# JETSON_PWR_MUX.net
KiCad netlist of a schematic drawn in Altium Designer
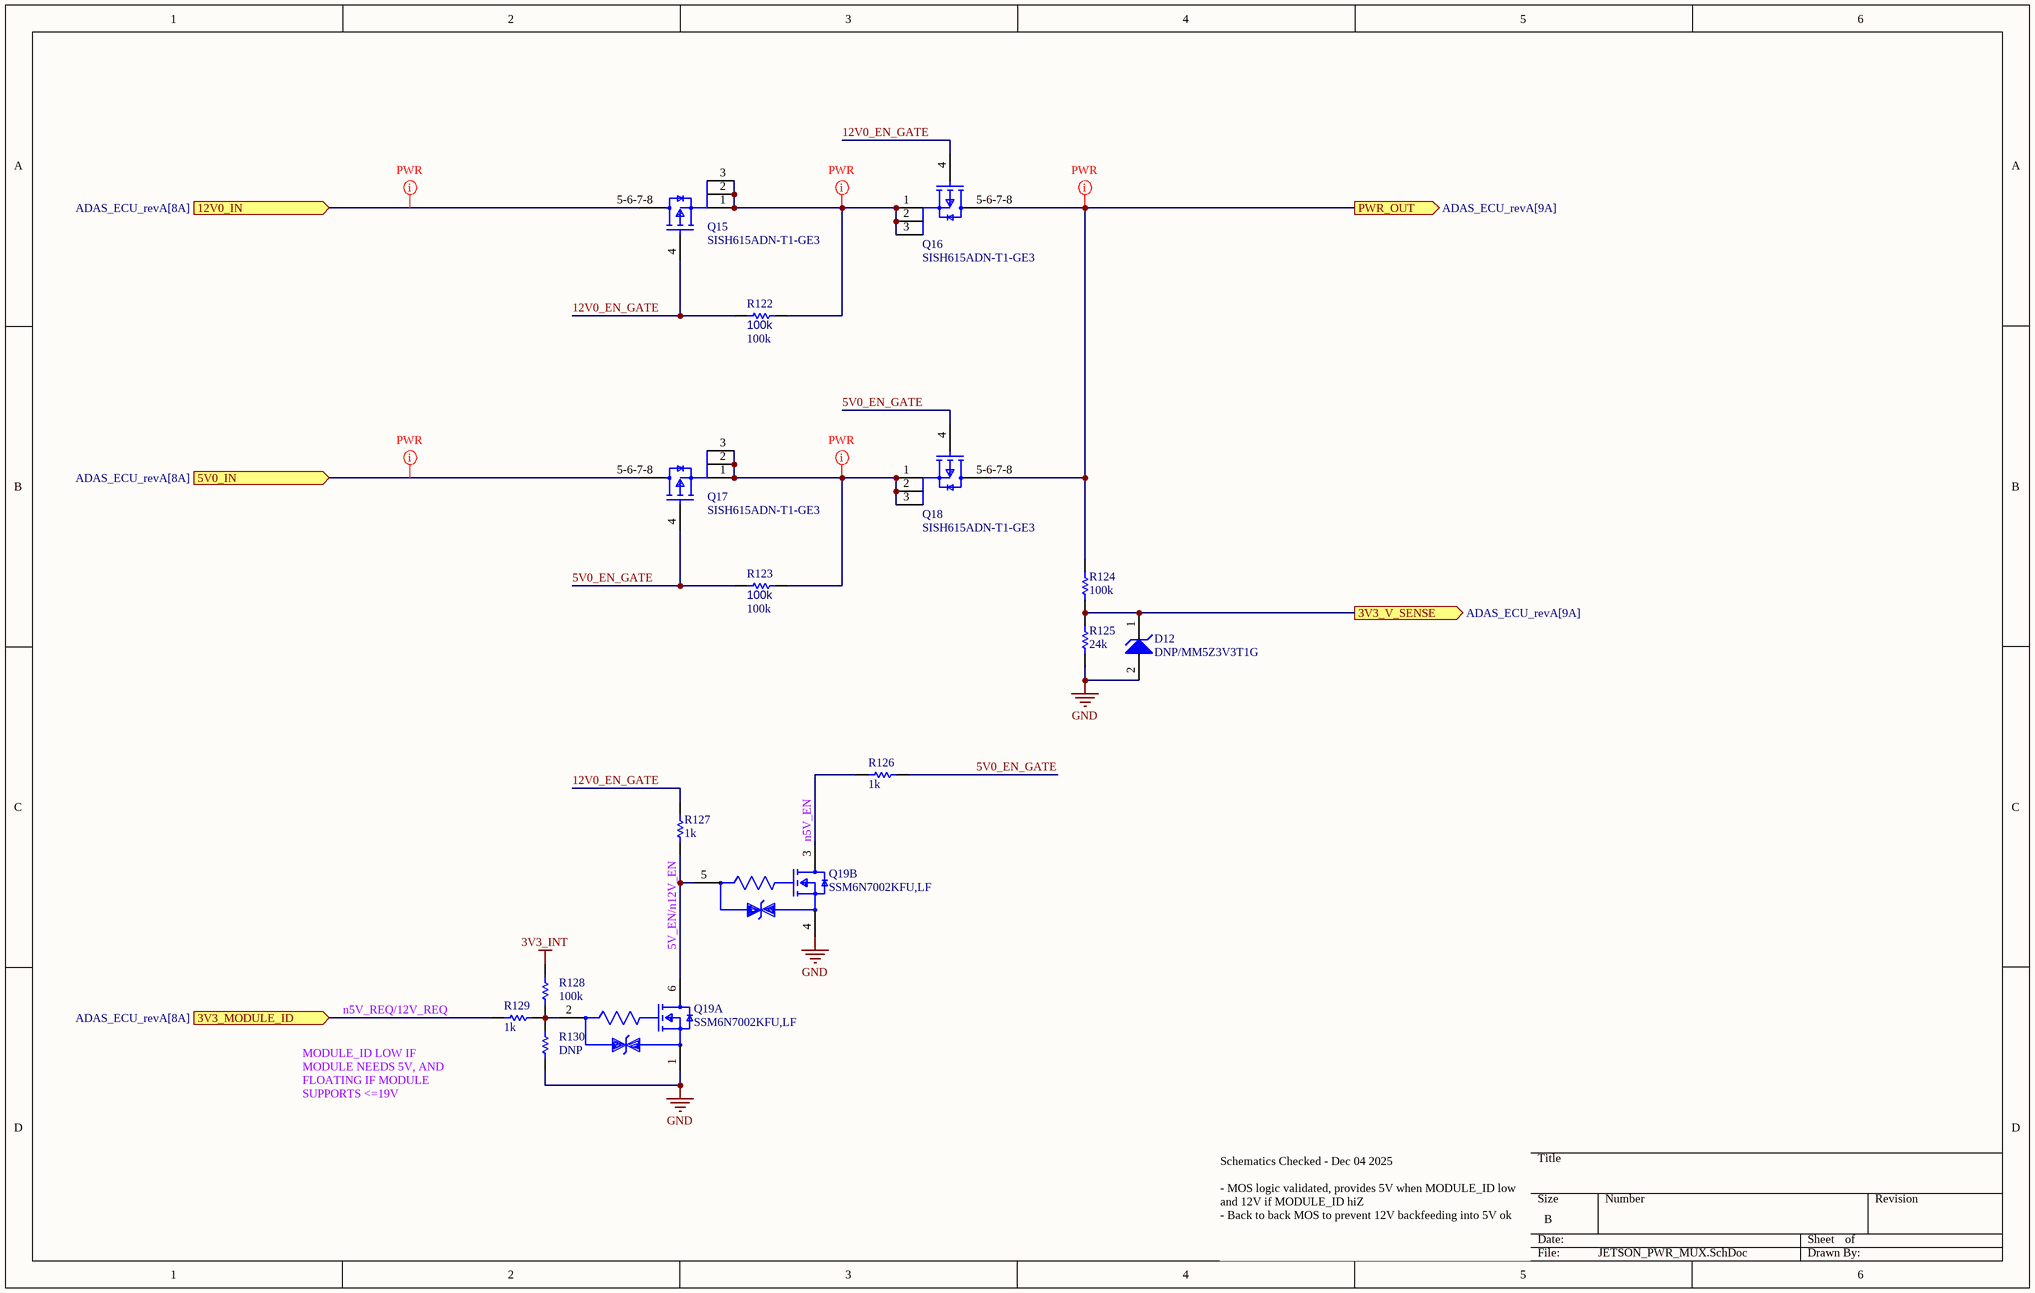
[diagram p0: JETSON_PWR_MUX.SchDoc]

(export (version "E")
  (design (tool "Eeschema 10.0.6"))
  (components
    (comp (ref "D12")
      (value "DNP/MM5Z3V3T1G")
      (footprint "ONSC-SOD-523-2-502-01_V")
      (description "Zener Voltage Regulator, 500 mW, 2-Pin SOD-523, Pb-Free, Tape and Reel")
      (fields (field (name "MANUFACTURER") "On Semiconductor") (field (name "PARTNUMBER") "MM5Z3V3T1G"))
      (libsource (lib "Altium Content Vault") (part "ONSC-K1A2-2"))
    )
    (comp (ref "Q15")
      (value "SISH615ADN-T1-GE3")
      (footprint "SISH615ADN-T1-GE3-Footprint-1")
      (description "Trans MOSFET P-CH 20V 22.1A 8-Pin PowerPAK 1212 EP T/R")
      (libsource (lib "Space Concordia") (part "CMP-013-00036-4"))
    )
    (comp (ref "Q16")
      (value "SISH615ADN-T1-GE3")
      (footprint "SISH615ADN-T1-GE3-Footprint-1")
      (description "Trans MOSFET P-CH 20V 22.1A 8-Pin PowerPAK 1212 EP T/R")
      (libsource (lib "Space Concordia") (part "CMP-013-00036-4"))
    )
    (comp (ref "Q17")
      (value "SISH615ADN-T1-GE3")
      (footprint "SISH615ADN-T1-GE3-Footprint-1")
      (description "Trans MOSFET P-CH 20V 22.1A 8-Pin PowerPAK 1212 EP T/R")
      (libsource (lib "Space Concordia") (part "CMP-013-00036-4"))
    )
    (comp (ref "Q18")
      (value "SISH615ADN-T1-GE3")
      (footprint "SISH615ADN-T1-GE3-Footprint-1")
      (description "Trans MOSFET P-CH 20V 22.1A 8-Pin PowerPAK 1212 EP T/R")
      (libsource (lib "Space Concordia") (part "CMP-013-00036-4"))
    )
    (comp (ref "Q19")
      (value "SSM6N7002KFU,LF")
      (footprint "FP-SSOP6-P-0_65A-MFG")
      (description "MOSFET 2N-CH 60V 0.3A")
      (libsource (lib "Altium Content Vault") (part "088aa6ac103fdeebe0d1c52ece6b7b9"))
    )
    (comp (ref "R122")
      (value "100k")
      (footprint "R0603B")
      (description "Resistor")
      (fields (field (name "ALTIUM_VALUE") "100k"))
      (libsource (lib "Space Concordia") (part "Resistor"))
    )
    (comp (ref "R123")
      (value "100k")
      (footprint "R0603B")
      (description "Resistor")
      (fields (field (name "ALTIUM_VALUE") "100k"))
      (libsource (lib "Space Concordia") (part "Resistor"))
    )
    (comp (ref "R124")
      (value "100k")
      (footprint "R0603B")
      (description "Resistor")
      (libsource (lib "Space Concordia") (part "Resistor"))
    )
    (comp (ref "R125")
      (value "24k")
      (footprint "R0603B")
      (description "Resistor")
      (libsource (lib "Space Concordia") (part "Resistor"))
    )
    (comp (ref "R126")
      (value "1k")
      (footprint "R0603B")
      (description "Resistor")
      (libsource (lib "Space Concordia") (part "Resistor"))
    )
    (comp (ref "R127")
      (value "1k")
      (footprint "R0603B")
      (description "Resistor")
      (libsource (lib "Space Concordia") (part "Resistor"))
    )
    (comp (ref "R128")
      (value "100k")
      (footprint "R0603B")
      (description "Resistor")
      (libsource (lib "Space Concordia") (part "Resistor"))
    )
    (comp (ref "R129")
      (value "1k")
      (footprint "R0603B")
      (description "Resistor")
      (libsource (lib "Space Concordia") (part "Resistor"))
    )
    (comp (ref "R130")
      (value "DNP")
      (footprint "R0603B")
      (description "Resistor")
      (libsource (lib "Space Concordia") (part "Resistor"))
    )
  )
  (nets
    (net (code "1") (name "/3V3_MODULE_ID") (class "Default")
      (node (ref "R129") (pin "1") (pinfunction "1_1") (pintype "passive"))
    )
    (net (code "2") (name "/3V3_V_SENSE") (class "Default")
      (node (ref "D12") (pin "1") (pinfunction "K_1") (pintype "passive"))
      (node (ref "R124") (pin "1") (pinfunction "1_1") (pintype "passive"))
      (node (ref "R125") (pin "2") (pinfunction "2_2") (pintype "passive"))
    )
    (net (code "3") (name "/5V0_EN_GATE") (class "Default")
      (node (ref "Q17") (pin "4") (pinfunction "G_4") (pintype "passive"))
      (node (ref "Q18") (pin "4") (pinfunction "G_4") (pintype "passive"))
      (node (ref "R123") (pin "2") (pinfunction "2_2") (pintype "passive"))
      (node (ref "R126") (pin "2") (pinfunction "2_2") (pintype "passive"))
    )
    (net (code "4") (name "/5V0_IN") (class "Default")
      (node (ref "Q17") (pin "5-6-7-8") (pinfunction "D_5-6-7-8") (pintype "passive"))
    )
    (net (code "5") (name "/12V0_EN_GATE") (class "Default")
      (node (ref "Q15") (pin "4") (pinfunction "G_4") (pintype "passive"))
      (node (ref "Q16") (pin "4") (pinfunction "G_4") (pintype "passive"))
      (node (ref "R122") (pin "2") (pinfunction "2_2") (pintype "passive"))
      (node (ref "R127") (pin "2") (pinfunction "2_2") (pintype "passive"))
    )
    (net (code "6") (name "/12V0_IN") (class "Default")
      (node (ref "Q15") (pin "5-6-7-8") (pinfunction "D_5-6-7-8") (pintype "passive"))
    )
    (net (code "7") (name "/PWR_OUT") (class "Default")
      (node (ref "Q16") (pin "5-6-7-8") (pinfunction "D_5-6-7-8") (pintype "passive"))
      (node (ref "Q18") (pin "5-6-7-8") (pinfunction "D_5-6-7-8") (pintype "passive"))
      (node (ref "R124") (pin "2") (pinfunction "2_2") (pintype "passive"))
    )
    (net (code "8") (name "3V3_INT") (class "Default")
      (node (ref "R128") (pin "1") (pinfunction "1_1") (pintype "passive"))
    )
    (net (code "9") (name "GND") (class "Default")
      (node (ref "D12") (pin "2") (pinfunction "A_2") (pintype "passive"))
      (node (ref "Q19") (pin "1") (pinfunction "Source1_1") (pintype "passive"))
      (node (ref "Q19") (pin "4") (pinfunction "Source2_4") (pintype "passive"))
      (node (ref "R125") (pin "1") (pinfunction "1_1") (pintype "passive"))
      (node (ref "R130") (pin "2") (pinfunction "2_2") (pintype "passive"))
    )
    (net (code "10") (name "Net-(Q15-S-Pad1)") (class "Default")
      (node (ref "Q15") (pin "1") (pinfunction "S_1") (pintype "passive"))
      (node (ref "Q15") (pin "2") (pinfunction "S_2") (pintype "passive"))
      (node (ref "Q15") (pin "3") (pinfunction "S_3") (pintype "passive"))
      (node (ref "Q16") (pin "1") (pinfunction "S_1") (pintype "passive"))
      (node (ref "Q16") (pin "2") (pinfunction "S_2") (pintype "passive"))
      (node (ref "Q16") (pin "3") (pinfunction "S_3") (pintype "passive"))
      (node (ref "R122") (pin "1") (pinfunction "1_1") (pintype "passive"))
    )
    (net (code "11") (name "Net-(Q17-S-Pad1)") (class "Default")
      (node (ref "Q17") (pin "1") (pinfunction "S_1") (pintype "passive"))
      (node (ref "Q17") (pin "2") (pinfunction "S_2") (pintype "passive"))
      (node (ref "Q17") (pin "3") (pinfunction "S_3") (pintype "passive"))
      (node (ref "Q18") (pin "1") (pinfunction "S_1") (pintype "passive"))
      (node (ref "Q18") (pin "2") (pinfunction "S_2") (pintype "passive"))
      (node (ref "Q18") (pin "3") (pinfunction "S_3") (pintype "passive"))
      (node (ref "R123") (pin "1") (pinfunction "1_1") (pintype "passive"))
    )
    (net (code "12") (name "Net-(Q19A-Drain1)") (class "Default")
      (node (ref "Q19") (pin "5") (pinfunction "Gate2_5") (pintype "passive"))
      (node (ref "Q19") (pin "6") (pinfunction "Drain1_6") (pintype "passive"))
      (node (ref "R127") (pin "1") (pinfunction "1_1") (pintype "passive"))
    )
    (net (code "13") (name "Net-(Q19A-Gate1)") (class "Default")
      (node (ref "Q19") (pin "2") (pinfunction "Gate1_2") (pintype "passive"))
      (node (ref "R128") (pin "2") (pinfunction "2_2") (pintype "passive"))
      (node (ref "R129") (pin "2") (pinfunction "2_2") (pintype "passive"))
      (node (ref "R130") (pin "1") (pinfunction "1_1") (pintype "passive"))
    )
    (net (code "14") (name "Net-(Q19B-Drain2)") (class "Default")
      (node (ref "Q19") (pin "3") (pinfunction "Drain2_3") (pintype "passive"))
      (node (ref "R126") (pin "1") (pinfunction "1_1") (pintype "passive"))
    )
  )
)
